# TSOC_MINIPROG_ADAPTER_R1_0.net
KiCad netlist of a schematic drawn in EAGLE
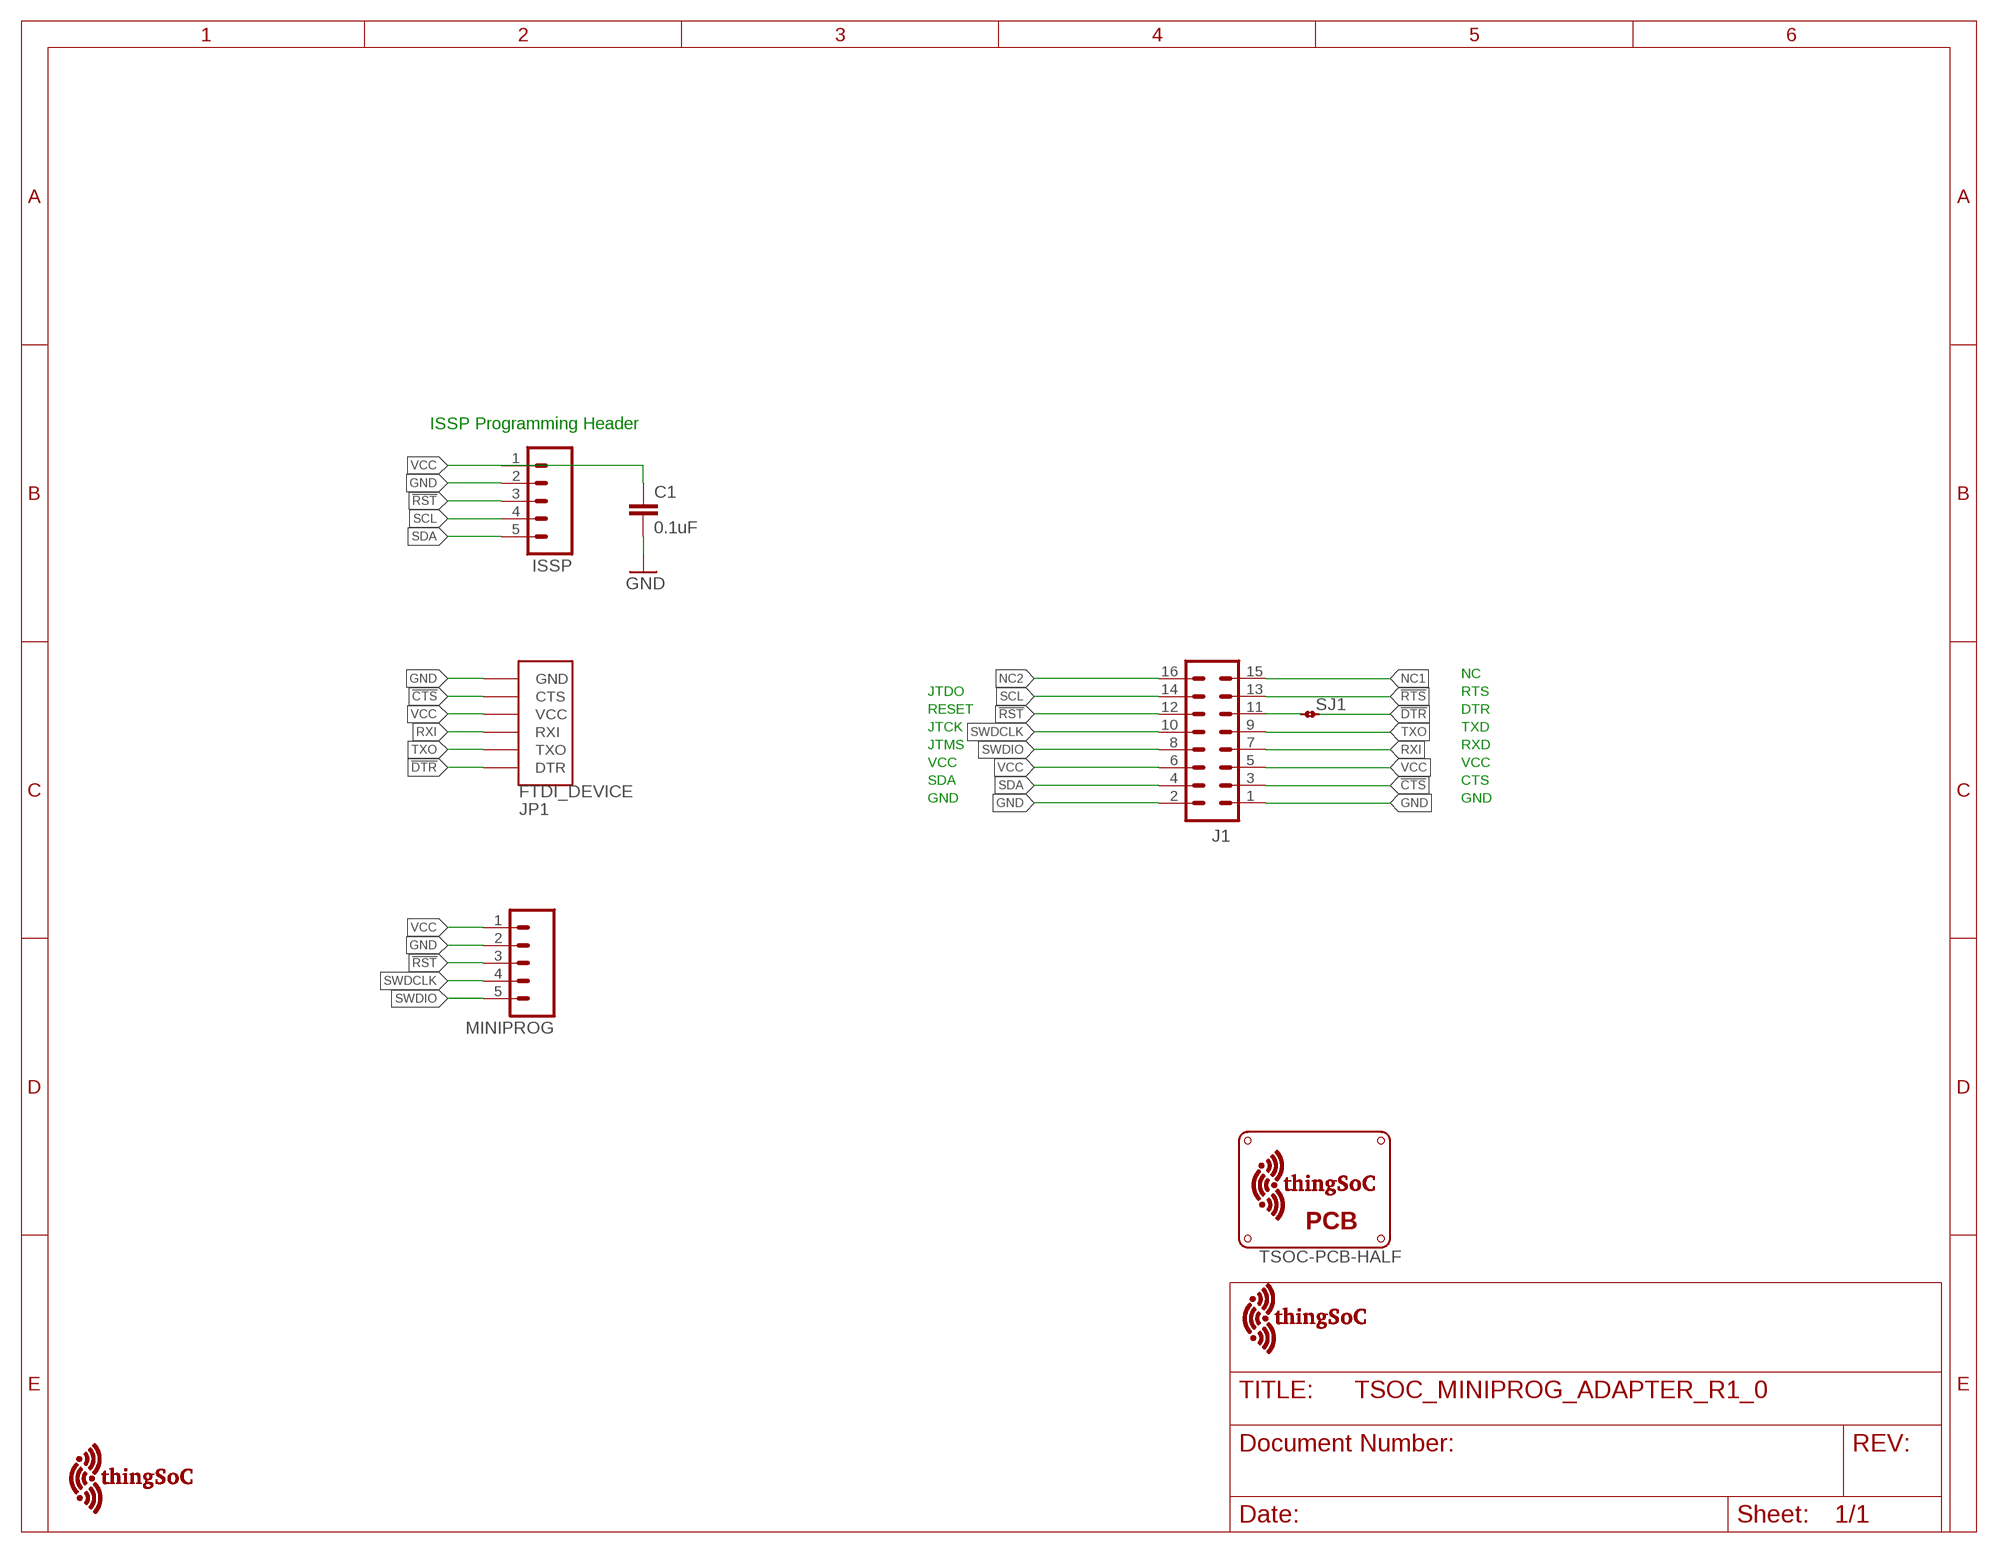
[diagram p0: schematic, sheet 1]

(export (version "E")
  (design (tool "Eeschema 10.0.6"))
  (components
    (comp (ref "C1")
      (value "0.1uF")
      (footprint "eagle-import:0603-CAP")
      (libsource (lib "eagle-import") (part "CAP0603-CAP"))
    )
    (comp (ref "ISSP")
      (value "M05PTH")
      (footprint "eagle-import:1X05")
      (libsource (lib "eagle-import") (part "M05PTH"))
    )
    (comp (ref "J1")
      (value "M08X2")
      (footprint "eagle-import:2X8")
      (libsource (lib "eagle-import") (part "M08X2"))
    )
    (comp (ref "JP1")
      (value "FTDI_DEVICE")
      (footprint "eagle-import:FTDI_DEVICE_SIDE")
      (libsource (lib "eagle-import") (part "FTDI_DEVICE"))
    )
    (comp (ref "MINIPROG")
      (value "M05PTH")
      (footprint "eagle-import:1X05")
      (libsource (lib "eagle-import") (part "SparkFun-Connectors_M05PTH"))
    )
    (comp (ref "SJ1")
      (value "JMP-2-NO")
      (footprint "eagle-import:JMP-2-NO")
      (libsource (lib "eagle-import") (part "JMP-2-NO"))
    )
    (comp (ref "U$3")
      (value "TSOC-LOGO-SMALL")
      (footprint "eagle-import:TSOC-LOGO-SML")
      (libsource (lib "eagle-import") (part "TSOC-LOGO-SMALL"))
    )
    (comp (ref "U$4")
      (value "TSOC-PCB-HALF")
      (footprint "eagle-import:TSOC-BB-BRD-HALF")
      (libsource (lib "eagle-import") (part "TSOC-PCB-HALF"))
    )
    (comp (ref "U$5")
      (value "TSOC-LOGO-SMALL")
      (footprint "eagle-import:TSOC-LOGO-SML")
      (libsource (lib "eagle-import") (part "TSOC-LOGO-SMALL"))
    )
    (comp (ref "U$6")
      (value "TSOC-LOGO-LRG")
      (footprint "eagle-import:TSOC-LOGO-LRG")
      (libsource (lib "eagle-import") (part "TSOC-LOGO-LRG"))
    )
  )
  (nets
    (net (code "1") (name "/~{CTS}") (class "Default")
      (node (ref "J1") (pin "3") (pinfunction "3_3") (pintype "passive"))
      (node (ref "JP1") (pin "P$5") (pinfunction "CTS_P$5") (pintype "bidirectional"))
    )
    (net (code "2") (name "/~{DTR}") (class "Default")
      (node (ref "JP1") (pin "P$1") (pinfunction "DTR_P$1") (pintype "bidirectional"))
      (node (ref "SJ1") (pin "2") (pinfunction "2_2") (pintype "passive"))
    )
    (net (code "3") (name "/~{RST}") (class "Default")
      (node (ref "ISSP") (pin "3") (pinfunction "3_3") (pintype "passive"))
      (node (ref "J1") (pin "12") (pinfunction "12_12") (pintype "passive"))
      (node (ref "MINIPROG") (pin "3") (pinfunction "3_3") (pintype "passive"))
    )
    (net (code "4") (name "/~{RTS}") (class "Default")
      (node (ref "J1") (pin "13") (pinfunction "13_13") (pintype "passive"))
    )
    (net (code "5") (name "GND") (class "Default")
      (node (ref "C1") (pin "2") (pinfunction "2_2") (pintype "passive"))
      (node (ref "ISSP") (pin "2") (pinfunction "2_2") (pintype "passive"))
      (node (ref "J1") (pin "1") (pinfunction "1_1") (pintype "passive"))
      (node (ref "J1") (pin "2") (pinfunction "2_2") (pintype "passive"))
      (node (ref "JP1") (pin "P$6") (pinfunction "GND_P$6") (pintype "bidirectional"))
      (node (ref "MINIPROG") (pin "2") (pinfunction "2_2") (pintype "passive"))
    )
    (net (code "6") (name "NC1") (class "Default")
      (node (ref "J1") (pin "15") (pinfunction "15_15") (pintype "passive"))
    )
    (net (code "7") (name "NC2") (class "Default")
      (node (ref "J1") (pin "16") (pinfunction "16_16") (pintype "passive"))
    )
    (net (code "8") (name "Net-(J1-Pad11)") (class "Default")
      (node (ref "J1") (pin "11") (pinfunction "11_11") (pintype "passive"))
      (node (ref "SJ1") (pin "1") (pinfunction "1_1") (pintype "passive"))
    )
    (net (code "9") (name "RXI") (class "Default")
      (node (ref "J1") (pin "7") (pinfunction "7_7") (pintype "passive"))
      (node (ref "JP1") (pin "P$3") (pinfunction "RXI_P$3") (pintype "bidirectional"))
    )
    (net (code "10") (name "SCL") (class "Default")
      (node (ref "ISSP") (pin "4") (pinfunction "4_4") (pintype "passive"))
      (node (ref "J1") (pin "14") (pinfunction "14_14") (pintype "passive"))
    )
    (net (code "11") (name "SDA") (class "Default")
      (node (ref "ISSP") (pin "5") (pinfunction "5_5") (pintype "passive"))
      (node (ref "J1") (pin "4") (pinfunction "4_4") (pintype "passive"))
    )
    (net (code "12") (name "SWDCLK") (class "Default")
      (node (ref "J1") (pin "10") (pinfunction "10_10") (pintype "passive"))
      (node (ref "MINIPROG") (pin "4") (pinfunction "4_4") (pintype "passive"))
    )
    (net (code "13") (name "SWDIO") (class "Default")
      (node (ref "J1") (pin "8") (pinfunction "8_8") (pintype "passive"))
      (node (ref "MINIPROG") (pin "5") (pinfunction "5_5") (pintype "passive"))
    )
    (net (code "14") (name "TXO") (class "Default")
      (node (ref "J1") (pin "9") (pinfunction "9_9") (pintype "passive"))
      (node (ref "JP1") (pin "P$2") (pinfunction "TXO_P$2") (pintype "bidirectional"))
    )
    (net (code "15") (name "VCC") (class "Default")
      (node (ref "C1") (pin "1") (pinfunction "1_1") (pintype "passive"))
      (node (ref "ISSP") (pin "1") (pinfunction "1_1") (pintype "passive"))
      (node (ref "J1") (pin "5") (pinfunction "5_5") (pintype "passive"))
      (node (ref "J1") (pin "6") (pinfunction "6_6") (pintype "passive"))
      (node (ref "JP1") (pin "P$4") (pinfunction "VCC_P$4") (pintype "bidirectional"))
      (node (ref "MINIPROG") (pin "1") (pinfunction "1_1") (pintype "passive"))
    )
  )
)
